# easyeda.net
KiCad netlist of a schematic drawn in EasyEDA
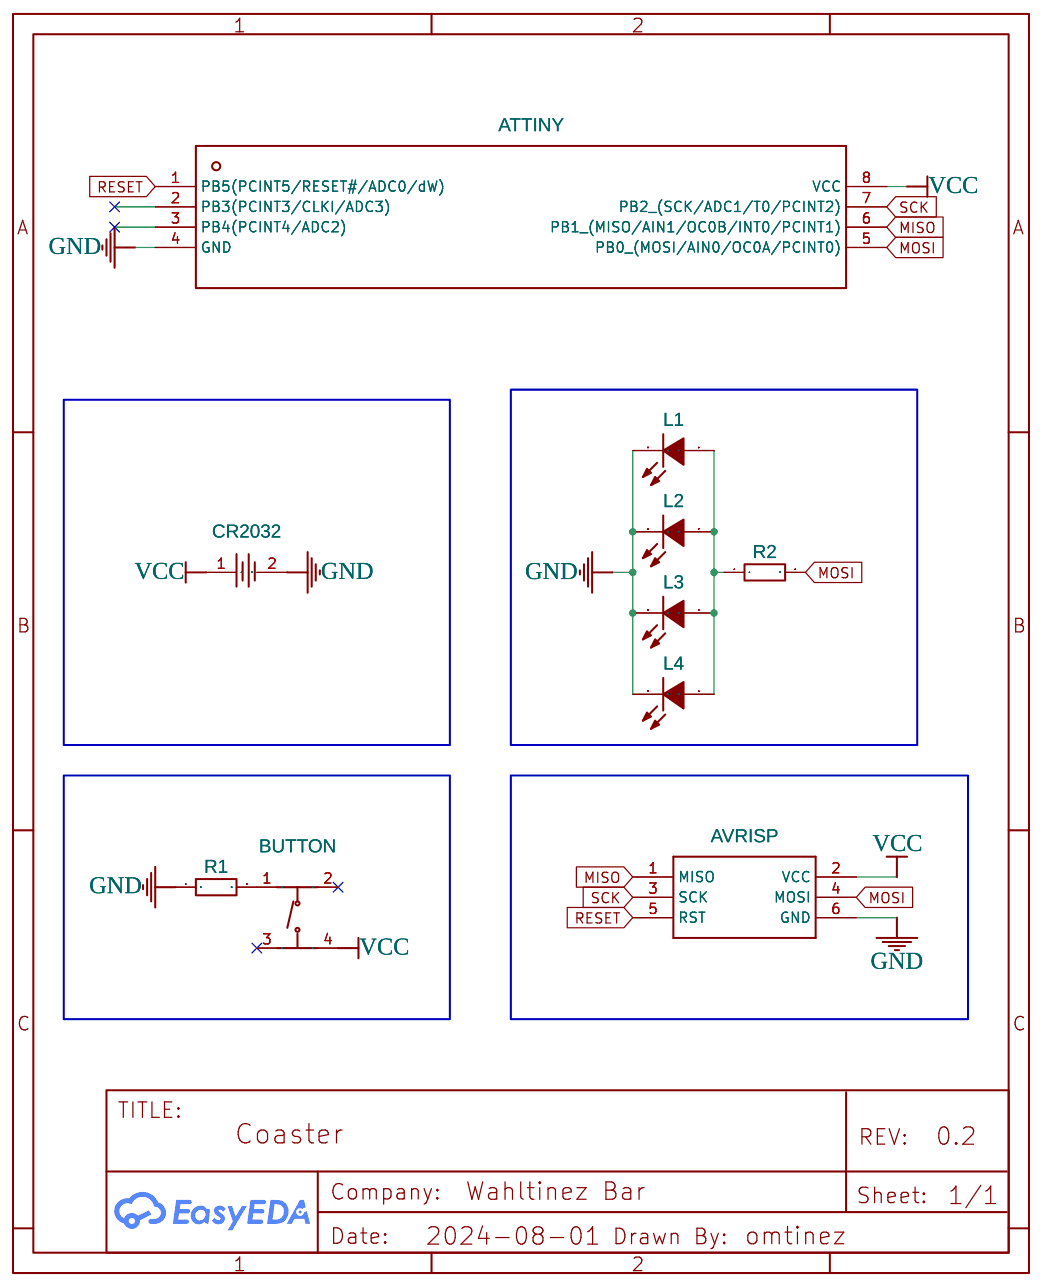
[diagram p0: schematic sheet]

(export (version "E")
  (design (tool "Eeschema 10.0.6"))
  (components
    (comp (ref "ATTINY")
      (value "ATTINY13A-SSUR")
      (fields (field (name "Manufacturer") "MICROCHIP(美国微芯)"))
      (libsource (lib "") (part "ATTINY13A-SSUR"))
    )
    (comp (ref "BUTTON")
      (value "TS-1187A-B-A-B")
      (fields (field (name "Manufacturer") "XKB Connectivity(中国星坤)"))
      (libsource (lib "") (part "TS-1187A-B-A-B"))
    )
    (comp (ref "CR2032")
      (value "MY-2032-12")
      (fields (field (name "Manufacturer") "MYOUNG(美阳)"))
      (libsource (lib "") (part "MY-2032-12"))
    )
    (comp (ref "ISP") (value "AVRISP") (libsource (lib "") (part "AVRISP")))
    (comp (ref "L1")
      (value "0603White light_C2290")
      (fields (field (name "Manufacturer Part") "KT-0603白灯") (field (name "Manufacturer") "KENTO"))
      (libsource (lib "") (part "0603White light_C2290"))
    )
    (comp (ref "L2")
      (value "0603White light_C2290")
      (fields (field (name "Manufacturer Part") "KT-0603白灯") (field (name "Manufacturer") "KENTO"))
      (libsource (lib "") (part "0603White light_C2290"))
    )
    (comp (ref "L3")
      (value "0603White light_C2290")
      (fields (field (name "Manufacturer Part") "KT-0603白灯") (field (name "Manufacturer") "KENTO"))
      (libsource (lib "") (part "0603White light_C2290"))
    )
    (comp (ref "L4")
      (value "0603White light_C2290")
      (fields (field (name "Manufacturer Part") "KT-0603白灯") (field (name "Manufacturer") "KENTO"))
      (libsource (lib "") (part "0603White light_C2290"))
    )
    (comp (ref "R1")
      (value "100mΩ")
      (fields
        (field (name "Manufacturer Part") "1206W4F100LT5E")
        (field (name "Manufacturer") "UNI-ROYAL(厚声)")
      )
      (libsource (lib "") (part "1206W4F100LT5E"))
    )
    (comp (ref "R2")
      (value "100mΩ")
      (fields
        (field (name "Manufacturer Part") "1206W4F100LT5E")
        (field (name "Manufacturer") "UNI-ROYAL(厚声)")
      )
      (libsource (lib "") (part "1206W4F100LT5E"))
    )
  )
  (nets
    (net (code "1") (name "GND") (class "Default")
      (node (ref "ATTINY") (pin "4") (pinfunction "GND_4") (pintype "unspecified"))
      (node (ref "CR2032") (pin "2") (pinfunction "2_2") (pintype "input"))
      (node (ref "ISP") (pin "6") (pinfunction "GND_6") (pintype "passive"))
      (node (ref "L1") (pin "2") (pinfunction "K_2") (pintype "unspecified"))
      (node (ref "L2") (pin "2") (pinfunction "K_2") (pintype "unspecified"))
      (node (ref "L3") (pin "2") (pinfunction "K_2") (pintype "unspecified"))
      (node (ref "L4") (pin "2") (pinfunction "K_2") (pintype "unspecified"))
      (node (ref "R1") (pin "1") (pinfunction "1_1") (pintype "input"))
    )
    (net (code "2") (name "MISO") (class "Default")
      (node (ref "ATTINY") (pin "6") (pinfunction "PB1_(MISO/AIN1/OC0B/INT0/PCINT1)_6") (pintype "unspecified"))
      (node (ref "ISP") (pin "1") (pinfunction "MISO_1") (pintype "input"))
    )
    (net (code "3") (name "MOSI") (class "Default")
      (node (ref "ATTINY") (pin "5") (pinfunction "PB0_(MOSI/AIN0/OC0A/PCINT0)_5") (pintype "unspecified"))
      (node (ref "ISP") (pin "4") (pinfunction "MOSI_4") (pintype "output"))
      (node (ref "R2") (pin "2") (pinfunction "2_2") (pintype "input"))
    )
    (net (code "4") (name "Net-(BUTTON-A)") (class "Default")
      (node (ref "BUTTON") (pin "1") (pinfunction "A_1") (pintype "unspecified"))
      (node (ref "R1") (pin "2") (pinfunction "2_2") (pintype "input"))
    )
    (net (code "5") (name "Net-(L1-A)") (class "Default")
      (node (ref "L1") (pin "1") (pinfunction "A_1") (pintype "unspecified"))
      (node (ref "L2") (pin "1") (pinfunction "A_1") (pintype "unspecified"))
      (node (ref "L3") (pin "1") (pinfunction "A_1") (pintype "unspecified"))
      (node (ref "L4") (pin "1") (pinfunction "A_1") (pintype "unspecified"))
      (node (ref "R2") (pin "1") (pinfunction "1_1") (pintype "input"))
    )
    (net (code "6") (name "RESET") (class "Default")
      (node (ref "ATTINY") (pin "1") (pinfunction "PB5(PCINT5/RESET#/ADC0/dW)_1") (pintype "unspecified"))
      (node (ref "ISP") (pin "5") (pinfunction "RST_5") (pintype "output"))
    )
    (net (code "7") (name "SCK") (class "Default")
      (node (ref "ATTINY") (pin "7") (pinfunction "PB2_(SCK/ADC1/T0/PCINT2)_7") (pintype "unspecified"))
      (node (ref "ISP") (pin "3") (pinfunction "SCK_3") (pintype "output"))
    )
    (net (code "8") (name "VCC") (class "Default")
      (node (ref "ATTINY") (pin "8") (pinfunction "VCC_8") (pintype "unspecified"))
      (node (ref "BUTTON") (pin "4") (pinfunction "D_4") (pintype "unspecified"))
      (node (ref "CR2032") (pin "1") (pinfunction "1_1") (pintype "input"))
      (node (ref "ISP") (pin "2") (pinfunction "VCC_2") (pintype "passive"))
    )
    (net (code "9") (name "unconnected-(ATTINY-PB3(PCINT3{slash}CLKI{slash}ADC3)-Pad2)") (class "Default")
      (node (ref "ATTINY") (pin "2") (pinfunction "PB3(PCINT3/CLKI/ADC3)_2") (pintype "unspecified+no_connect"))
    )
    (net (code "10") (name "unconnected-(ATTINY-PB4(PCINT4{slash}ADC2)-Pad3)") (class "Default")
      (node (ref "ATTINY") (pin "3") (pinfunction "PB4(PCINT4/ADC2)_3") (pintype "unspecified+no_connect"))
    )
    (net (code "11") (name "unconnected-(BUTTON-B-Pad2)") (class "Default")
      (node (ref "BUTTON") (pin "2") (pinfunction "B_2") (pintype "unspecified+no_connect"))
    )
    (net (code "12") (name "unconnected-(BUTTON-C-Pad3)") (class "Default")
      (node (ref "BUTTON") (pin "3") (pinfunction "C_3") (pintype "unspecified+no_connect"))
    )
  )
)
